# CMSIS-DAP_V1.net
KiCad netlist of a schematic drawn in EAGLE
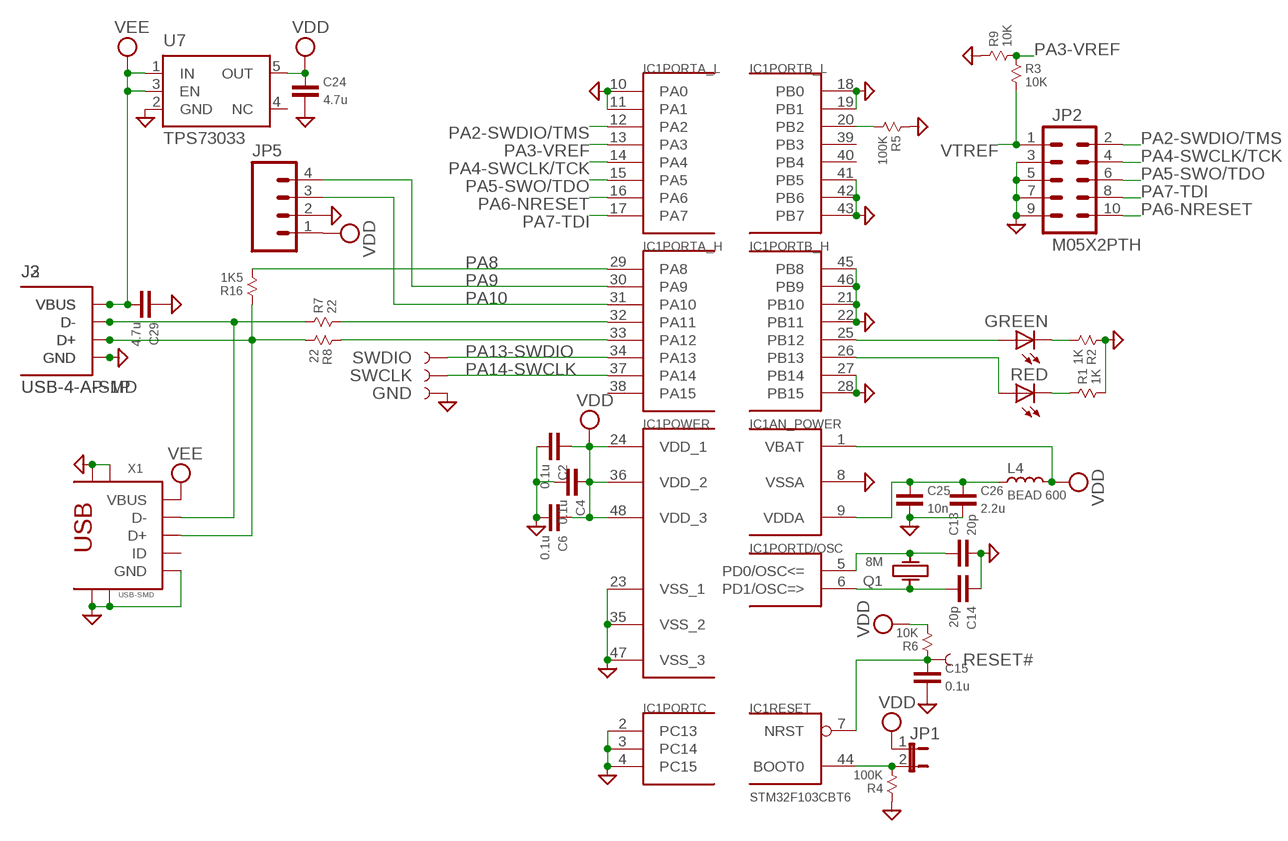
[diagram p0: schematic, sheet 1]

(export (version "E")
  (design (tool "Eeschema 10.0.6"))
  (components
    (comp (ref "C2")
      (value "0.1u")
      (footprint "eagle-import:0603")
      (libsource (lib "eagle-import") (part "CAP-0603"))
    )
    (comp (ref "C4")
      (value "0.1u")
      (footprint "eagle-import:0603")
      (libsource (lib "eagle-import") (part "CAP-0603"))
    )
    (comp (ref "C6")
      (value "0.1u")
      (footprint "eagle-import:0603")
      (libsource (lib "eagle-import") (part "CAP-0603"))
    )
    (comp (ref "C13")
      (value "20p")
      (footprint "eagle-import:0603")
      (libsource (lib "eagle-import") (part "CAP-0603"))
    )
    (comp (ref "C14")
      (value "20p")
      (footprint "eagle-import:0603")
      (libsource (lib "eagle-import") (part "CAP-0603"))
    )
    (comp (ref "C15")
      (value "0.1u")
      (footprint "eagle-import:0603")
      (libsource (lib "eagle-import") (part "CAP-0603"))
    )
    (comp (ref "C24")
      (value "4.7u")
      (footprint "eagle-import:0603")
      (libsource (lib "eagle-import") (part "CAP-0603"))
    )
    (comp (ref "C25")
      (value "10n")
      (footprint "eagle-import:0603")
      (libsource (lib "eagle-import") (part "CAP-0603"))
    )
    (comp (ref "C26")
      (value "2.2u")
      (footprint "eagle-import:0603")
      (libsource (lib "eagle-import") (part "CAP-0603"))
    )
    (comp (ref "C29")
      (value "4.7u")
      (footprint "eagle-import:0603")
      (libsource (lib "eagle-import") (part "CAP-0603"))
    )
    (comp (ref "GND")
      (value "TEST-POINT1")
      (footprint "eagle-import:PAD.1X1")
      (libsource (lib "eagle-import") (part "TEST-POINT1"))
    )
    (comp (ref "GREEN")
      (value "LEDCHIPLED_0603")
      (footprint "eagle-import:CHIPLED_0603")
      (libsource (lib "eagle-import") (part "LEDCHIPLED_0603"))
    )
    (comp (ref "IC1")
      (value "STM32F103CBT6")
      (footprint "eagle-import:TQFP48")
      (libsource (lib "eagle-import") (part "STM32F10XCXT6"))
    )
    (comp (ref "J2")
      (value "USB-4-AP-1P")
      (footprint "eagle-import:USBAP-1P")
      (libsource (lib "eagle-import") (part "USB-4-AP-1P"))
    )
    (comp (ref "J3")
      (value "USB-4-A-SMD")
      (footprint "eagle-import:USB-A-SMD")
      (libsource (lib "eagle-import") (part "USB-4-A-SMD"))
    )
    (comp (ref "JP1")
      (value "JUMPER-2SMD-NO")
      (footprint "eagle-import:SJ_2S-NO")
      (libsource (lib "eagle-import") (part "JUMPER-2SMD-NO"))
    )
    (comp (ref "JP2")
      (value "M05X2PTH")
      (footprint "eagle-import:AVR_ICSP")
      (libsource (lib "eagle-import") (part "M05X2PTH"))
    )
    (comp (ref "JP5")
      (value "M04PTH")
      (footprint "eagle-import:1X04")
      (libsource (lib "eagle-import") (part "M04PTH"))
    )
    (comp (ref "L4")
      (value "BEAD 600")
      (footprint "eagle-import:0603")
      (libsource (lib "eagle-import") (part "INDUCTOR-0603"))
    )
    (comp (ref "Q1")
      (value "8M")
      (footprint "eagle-import:KX-9A")
      (libsource (lib "eagle-import") (part "CRYSTAL-KX-9A"))
    )
    (comp (ref "R1")
      (value "1K")
      (footprint "eagle-import:0603")
      (libsource (lib "eagle-import") (part "RESISTOR-0603"))
    )
    (comp (ref "R2")
      (value "1K")
      (footprint "eagle-import:0603")
      (libsource (lib "eagle-import") (part "RESISTOR-0603"))
    )
    (comp (ref "R3")
      (value "10K")
      (footprint "eagle-import:0603")
      (libsource (lib "eagle-import") (part "RESISTOR-0603"))
    )
    (comp (ref "R4")
      (value "100K")
      (footprint "eagle-import:0603")
      (libsource (lib "eagle-import") (part "RESISTOR-0603"))
    )
    (comp (ref "R5")
      (value "100K")
      (footprint "eagle-import:0603")
      (libsource (lib "eagle-import") (part "RESISTOR-0603"))
    )
    (comp (ref "R6")
      (value "10K")
      (footprint "eagle-import:0603")
      (libsource (lib "eagle-import") (part "RESISTOR-0603"))
    )
    (comp (ref "R7")
      (value "22")
      (footprint "eagle-import:0603")
      (libsource (lib "eagle-import") (part "RESISTOR-0603"))
    )
    (comp (ref "R8")
      (value "22")
      (footprint "eagle-import:0603")
      (libsource (lib "eagle-import") (part "RESISTOR-0603"))
    )
    (comp (ref "R9")
      (value "10K")
      (footprint "eagle-import:0603")
      (libsource (lib "eagle-import") (part "RESISTOR-0603"))
    )
    (comp (ref "R16")
      (value "1K5")
      (footprint "eagle-import:0603")
      (libsource (lib "eagle-import") (part "RESISTOR-0603"))
    )
    (comp (ref "RED")
      (value "LEDCHIPLED_0603")
      (footprint "eagle-import:CHIPLED_0603")
      (libsource (lib "eagle-import") (part "LEDCHIPLED_0603"))
    )
    (comp (ref "RESET#")
      (value "TEST-POINT3")
      (footprint "eagle-import:PAD.03X.03")
      (libsource (lib "eagle-import") (part "TEST-POINT3"))
    )
    (comp (ref "SWCLK")
      (value "TEST-POINT1")
      (footprint "eagle-import:PAD.1X1")
      (libsource (lib "eagle-import") (part "TEST-POINT1"))
    )
    (comp (ref "SWDIO")
      (value "TEST-POINT1")
      (footprint "eagle-import:PAD.1X1")
      (libsource (lib "eagle-import") (part "TEST-POINT1"))
    )
    (comp (ref "U7")
      (value "TPS73033")
      (footprint "eagle-import:SOT23-5")
      (libsource (lib "eagle-import") (part "TPS73033"))
    )
    (comp (ref "X1")
      (value "USB-SMD")
      (footprint "eagle-import:USB-MINIB")
      (libsource (lib "eagle-import") (part "USB-SMD"))
    )
  )
  (nets
    (net (code "1") (name "/PA2-SWDIO{slash}TMS") (class "Default")
      (node (ref "IC1") (pin "12") (pinfunction "PA2_12") (pintype "bidirectional"))
      (node (ref "JP2") (pin "2") (pinfunction "2_2") (pintype "passive"))
    )
    (net (code "2") (name "/PA3-VREF") (class "Default")
      (node (ref "IC1") (pin "13") (pinfunction "PA3_13") (pintype "bidirectional"))
      (node (ref "R3") (pin "1") (pinfunction "1_1") (pintype "passive"))
      (node (ref "R9") (pin "2") (pinfunction "2_2") (pintype "passive"))
    )
    (net (code "3") (name "/PA4-SWCLK{slash}TCK") (class "Default")
      (node (ref "IC1") (pin "14") (pinfunction "PA4_14") (pintype "bidirectional"))
      (node (ref "JP2") (pin "4") (pinfunction "4_4") (pintype "passive"))
    )
    (net (code "4") (name "/PA5-SWO{slash}TDO") (class "Default")
      (node (ref "IC1") (pin "15") (pinfunction "PA5_15") (pintype "bidirectional"))
      (node (ref "JP2") (pin "6") (pinfunction "6_6") (pintype "passive"))
    )
    (net (code "5") (name "/PA6-NRESET") (class "Default")
      (node (ref "IC1") (pin "16") (pinfunction "PA6_16") (pintype "bidirectional"))
      (node (ref "JP2") (pin "10") (pinfunction "10_10") (pintype "passive"))
    )
    (net (code "6") (name "/PA7-TDI") (class "Default")
      (node (ref "IC1") (pin "17") (pinfunction "PA7_17") (pintype "bidirectional"))
      (node (ref "JP2") (pin "8") (pinfunction "8_8") (pintype "passive"))
    )
    (net (code "7") (name "/PA8") (class "Default")
      (node (ref "IC1") (pin "29") (pinfunction "PA8_29") (pintype "bidirectional"))
      (node (ref "R16") (pin "2") (pinfunction "2_2") (pintype "passive"))
    )
    (net (code "8") (name "/PA9") (class "Default")
      (node (ref "IC1") (pin "30") (pinfunction "PA9_30") (pintype "bidirectional"))
      (node (ref "JP5") (pin "4") (pinfunction "4_4") (pintype "passive"))
    )
    (net (code "9") (name "/PA10") (class "Default")
      (node (ref "IC1") (pin "31") (pinfunction "PA10_31") (pintype "bidirectional"))
      (node (ref "JP5") (pin "3") (pinfunction "3_3") (pintype "passive"))
    )
    (net (code "10") (name "/PA13-SWDIO") (class "Default")
      (node (ref "IC1") (pin "34") (pinfunction "PA13_34") (pintype "bidirectional"))
      (node (ref "SWDIO") (pin "P$1") (pinfunction "1_P$1") (pintype "bidirectional"))
    )
    (net (code "11") (name "/PA14-SWCLK") (class "Default")
      (node (ref "IC1") (pin "37") (pinfunction "PA14_37") (pintype "bidirectional"))
      (node (ref "SWCLK") (pin "P$1") (pinfunction "1_P$1") (pintype "bidirectional"))
    )
    (net (code "12") (name "/VTREF") (class "Default")
      (node (ref "JP2") (pin "1") (pinfunction "1_1") (pintype "passive"))
      (node (ref "R3") (pin "2") (pinfunction "2_2") (pintype "passive"))
    )
    (net (code "13") (name "GND") (class "Default")
      (node (ref "C13") (pin "1") (pinfunction "1_1") (pintype "passive"))
      (node (ref "C14") (pin "2") (pinfunction "2_2") (pintype "passive"))
      (node (ref "C15") (pin "1") (pinfunction "1_1") (pintype "passive"))
      (node (ref "C2") (pin "1") (pinfunction "1_1") (pintype "passive"))
      (node (ref "C24") (pin "1") (pinfunction "1_1") (pintype "passive"))
      (node (ref "C25") (pin "1") (pinfunction "1_1") (pintype "passive"))
      (node (ref "C26") (pin "1") (pinfunction "1_1") (pintype "passive"))
      (node (ref "C29") (pin "2") (pinfunction "2_2") (pintype "passive"))
      (node (ref "C4") (pin "1") (pinfunction "1_1") (pintype "passive"))
      (node (ref "C6") (pin "1") (pinfunction "1_1") (pintype "passive"))
      (node (ref "GND") (pin "P$1") (pinfunction "1_P$1") (pintype "bidirectional"))
      (node (ref "IC1") (pin "10") (pinfunction "PA0_10") (pintype "bidirectional"))
      (node (ref "IC1") (pin "11") (pinfunction "PA1_11") (pintype "bidirectional"))
      (node (ref "IC1") (pin "18") (pinfunction "PB0_18") (pintype "bidirectional"))
      (node (ref "IC1") (pin "19") (pinfunction "PB1_19") (pintype "bidirectional"))
      (node (ref "IC1") (pin "2") (pinfunction "PC13_2") (pintype "bidirectional"))
      (node (ref "IC1") (pin "21") (pinfunction "PB10_21") (pintype "bidirectional"))
      (node (ref "IC1") (pin "22") (pinfunction "PB11_22") (pintype "bidirectional"))
      (node (ref "IC1") (pin "23") (pinfunction "VSS_1_23") (pintype "power_in"))
      (node (ref "IC1") (pin "27") (pinfunction "PB14_27") (pintype "bidirectional"))
      (node (ref "IC1") (pin "28") (pinfunction "PB15_28") (pintype "bidirectional"))
      (node (ref "IC1") (pin "3") (pinfunction "PC14_3") (pintype "bidirectional"))
      (node (ref "IC1") (pin "35") (pinfunction "VSS_2_35") (pintype "power_in"))
      (node (ref "IC1") (pin "4") (pinfunction "PC15_4") (pintype "bidirectional"))
      (node (ref "IC1") (pin "41") (pinfunction "PB5_41") (pintype "bidirectional"))
      (node (ref "IC1") (pin "42") (pinfunction "PB6_42") (pintype "bidirectional"))
      (node (ref "IC1") (pin "43") (pinfunction "PB7_43") (pintype "bidirectional"))
      (node (ref "IC1") (pin "45") (pinfunction "PB8_45") (pintype "bidirectional"))
      (node (ref "IC1") (pin "46") (pinfunction "PB9_46") (pintype "bidirectional"))
      (node (ref "IC1") (pin "47") (pinfunction "VSS_3_47") (pintype "power_in"))
      (node (ref "IC1") (pin "8") (pinfunction "VSSA_8") (pintype "power_in"))
      (node (ref "J2") (pin "GND") (pinfunction "GND_GND") (pintype "power_in"))
      (node (ref "J3") (pin "GND") (pinfunction "GND_GND") (pintype "power_in"))
      (node (ref "JP2") (pin "3") (pinfunction "3_3") (pintype "passive"))
      (node (ref "JP2") (pin "5") (pinfunction "5_5") (pintype "passive"))
      (node (ref "JP2") (pin "7") (pinfunction "7_7") (pintype "passive"))
      (node (ref "JP2") (pin "9") (pinfunction "9_9") (pintype "passive"))
      (node (ref "JP5") (pin "2") (pinfunction "2_2") (pintype "passive"))
      (node (ref "R1") (pin "2") (pinfunction "2_2") (pintype "passive"))
      (node (ref "R2") (pin "1") (pinfunction "1_1") (pintype "passive"))
      (node (ref "R4") (pin "1") (pinfunction "1_1") (pintype "passive"))
      (node (ref "R5") (pin "1") (pinfunction "1_1") (pintype "passive"))
      (node (ref "R9") (pin "1") (pinfunction "1_1") (pintype "passive"))
      (node (ref "U7") (pin "2") (pinfunction "GND_2") (pintype "power_in"))
      (node (ref "X1") (pin "GND") (pinfunction "GND_GND") (pintype "power_in"))
      (node (ref "X1") (pin "GND@1") (pinfunction "GND_GND@1") (pintype "power_in"))
      (node (ref "X1") (pin "GND@2") (pinfunction "GND_GND@2") (pintype "power_in"))
      (node (ref "X1") (pin "GND@3") (pinfunction "GND_GND@3") (pintype "power_in"))
      (node (ref "X1") (pin "GND@4") (pinfunction "GND_GND@4") (pintype "power_in"))
    )
    (net (code "14") (name "Net-(GREEN-PadC)") (class "Default")
      (node (ref "GREEN") (pin "C") (pinfunction "C_C") (pintype "passive"))
      (node (ref "R2") (pin "2") (pinfunction "2_2") (pintype "passive"))
    )
    (net (code "15") (name "Net-(IC1A-VDDA)") (class "Default")
      (node (ref "C25") (pin "2") (pinfunction "2_2") (pintype "passive"))
      (node (ref "C26") (pin "2") (pinfunction "2_2") (pintype "passive"))
      (node (ref "IC1") (pin "9") (pinfunction "VDDA_9") (pintype "power_in"))
      (node (ref "L4") (pin "1") (pinfunction "1_1") (pintype "passive"))
    )
    (net (code "16") (name "Net-(IC1B-PA11)") (class "Default")
      (node (ref "IC1") (pin "32") (pinfunction "PA11_32") (pintype "bidirectional"))
      (node (ref "R7") (pin "2") (pinfunction "2_2") (pintype "passive"))
    )
    (net (code "17") (name "Net-(IC1B-PA12)") (class "Default")
      (node (ref "IC1") (pin "33") (pinfunction "PA12_33") (pintype "bidirectional"))
      (node (ref "R8") (pin "1") (pinfunction "1_1") (pintype "passive"))
    )
    (net (code "18") (name "Net-(IC1D-PB12)") (class "Default")
      (node (ref "GREEN") (pin "A") (pinfunction "A_A") (pintype "passive"))
      (node (ref "IC1") (pin "25") (pinfunction "PB12_25") (pintype "bidirectional"))
    )
    (net (code "19") (name "Net-(IC1D-PB13)") (class "Default")
      (node (ref "IC1") (pin "26") (pinfunction "PB13_26") (pintype "bidirectional"))
      (node (ref "RED") (pin "A") (pinfunction "A_A") (pintype "passive"))
    )
    (net (code "20") (name "Net-(IC1E-PB2)") (class "Default")
      (node (ref "IC1") (pin "20") (pinfunction "PB2_20") (pintype "bidirectional"))
      (node (ref "R5") (pin "2") (pinfunction "2_2") (pintype "passive"))
    )
    (net (code "21") (name "Net-(IC1G-PD0{slash}OSC<=)") (class "Default")
      (node (ref "C13") (pin "2") (pinfunction "2_2") (pintype "passive"))
      (node (ref "IC1") (pin "5") (pinfunction "PD0/OSC<=_5") (pintype "bidirectional"))
      (node (ref "Q1") (pin "3") (pinfunction "2_3") (pintype "passive"))
    )
    (net (code "22") (name "Net-(IC1G-PD1{slash}OSC=>)") (class "Default")
      (node (ref "C14") (pin "1") (pinfunction "1_1") (pintype "passive"))
      (node (ref "IC1") (pin "6") (pinfunction "PD1/OSC=>_6") (pintype "bidirectional"))
      (node (ref "Q1") (pin "1") (pinfunction "1_1") (pintype "passive"))
    )
    (net (code "23") (name "Net-(IC1I-BOOT0)") (class "Default")
      (node (ref "IC1") (pin "44") (pinfunction "BOOT0_44") (pintype "input"))
      (node (ref "JP1") (pin "2") (pinfunction "2_2") (pintype "passive"))
      (node (ref "R4") (pin "2") (pinfunction "2_2") (pintype "passive"))
    )
    (net (code "24") (name "Net-(IC1I-NRST)") (class "Default")
      (node (ref "C15") (pin "2") (pinfunction "2_2") (pintype "passive"))
      (node (ref "IC1") (pin "7") (pinfunction "NRST_7") (pintype "input"))
      (node (ref "R6") (pin "1") (pinfunction "1_1") (pintype "passive"))
      (node (ref "RESET#") (pin "P$1") (pinfunction "1_P$1") (pintype "bidirectional"))
    )
    (net (code "25") (name "Net-(J2-PadD+)") (class "Default")
      (node (ref "J2") (pin "D+") (pinfunction "D+_D+") (pintype "bidirectional"))
      (node (ref "J3") (pin "D+") (pinfunction "D+_D+") (pintype "bidirectional"))
      (node (ref "R16") (pin "1") (pinfunction "1_1") (pintype "passive"))
      (node (ref "R8") (pin "2") (pinfunction "2_2") (pintype "passive"))
      (node (ref "X1") (pin "D+") (pinfunction "D+_D+") (pintype "bidirectional"))
    )
    (net (code "26") (name "Net-(J2-PadD-)") (class "Default")
      (node (ref "J2") (pin "D-") (pinfunction "D-_D-") (pintype "bidirectional"))
      (node (ref "J3") (pin "D-") (pinfunction "D-_D-") (pintype "bidirectional"))
      (node (ref "R7") (pin "1") (pinfunction "1_1") (pintype "passive"))
      (node (ref "X1") (pin "D-") (pinfunction "D-_D-") (pintype "bidirectional"))
    )
    (net (code "27") (name "Net-(R1-Pad1)") (class "Default")
      (node (ref "R1") (pin "1") (pinfunction "1_1") (pintype "passive"))
      (node (ref "RED") (pin "C") (pinfunction "C_C") (pintype "passive"))
    )
    (net (code "28") (name "VDD") (class "Default")
      (node (ref "C2") (pin "2") (pinfunction "2_2") (pintype "passive"))
      (node (ref "C24") (pin "2") (pinfunction "2_2") (pintype "passive"))
      (node (ref "C4") (pin "2") (pinfunction "2_2") (pintype "passive"))
      (node (ref "C6") (pin "2") (pinfunction "2_2") (pintype "passive"))
      (node (ref "IC1") (pin "1") (pinfunction "VBAT_1") (pintype "power_in"))
      (node (ref "IC1") (pin "24") (pinfunction "VDD_1_24") (pintype "power_in"))
      (node (ref "IC1") (pin "36") (pinfunction "VDD_2_36") (pintype "power_in"))
      (node (ref "IC1") (pin "48") (pinfunction "VDD_3_48") (pintype "power_in"))
      (node (ref "JP1") (pin "1") (pinfunction "1_1") (pintype "passive"))
      (node (ref "JP5") (pin "1") (pinfunction "1_1") (pintype "passive"))
      (node (ref "L4") (pin "2") (pinfunction "2_2") (pintype "passive"))
      (node (ref "R6") (pin "2") (pinfunction "2_2") (pintype "passive"))
      (node (ref "U7") (pin "5") (pinfunction "OUT_5") (pintype "passive"))
    )
    (net (code "29") (name "VEE") (class "Default")
      (node (ref "C29") (pin "1") (pinfunction "1_1") (pintype "passive"))
      (node (ref "J2") (pin "VBUS") (pinfunction "VBUS_VBUS") (pintype "passive"))
      (node (ref "J3") (pin "VUSB") (pinfunction "VBUS_VUSB") (pintype "passive"))
      (node (ref "U7") (pin "1") (pinfunction "IN_1") (pintype "passive"))
      (node (ref "U7") (pin "3") (pinfunction "EN_3") (pintype "input"))
      (node (ref "X1") (pin "VBUS") (pinfunction "VBUS_VBUS") (pintype "passive"))
    )
    (net (code "30") (name "unconnected-(IC1B-PA15-Pad38)") (class "Default")
      (node (ref "IC1") (pin "38") (pinfunction "PA15_38") (pintype "bidirectional"))
    )
    (net (code "31") (name "unconnected-(IC1E-PB3-Pad39)") (class "Default")
      (node (ref "IC1") (pin "39") (pinfunction "PB3_39") (pintype "bidirectional"))
    )
    (net (code "32") (name "unconnected-(IC1E-PB4-Pad40)") (class "Default")
      (node (ref "IC1") (pin "40") (pinfunction "PB4_40") (pintype "bidirectional"))
    )
    (net (code "33") (name "unconnected-(U7-NC-Pad4)") (class "Default")
      (node (ref "U7") (pin "4") (pinfunction "NC_4") (pintype "no_connect"))
    )
    (net (code "34") (name "unconnected-(X1-PadID)") (class "Default")
      (node (ref "X1") (pin "ID") (pinfunction "ID_ID") (pintype "bidirectional"))
    )
  )
)
